# 6_Power_Output.net
KiCad netlist of a schematic drawn in Altium Designer
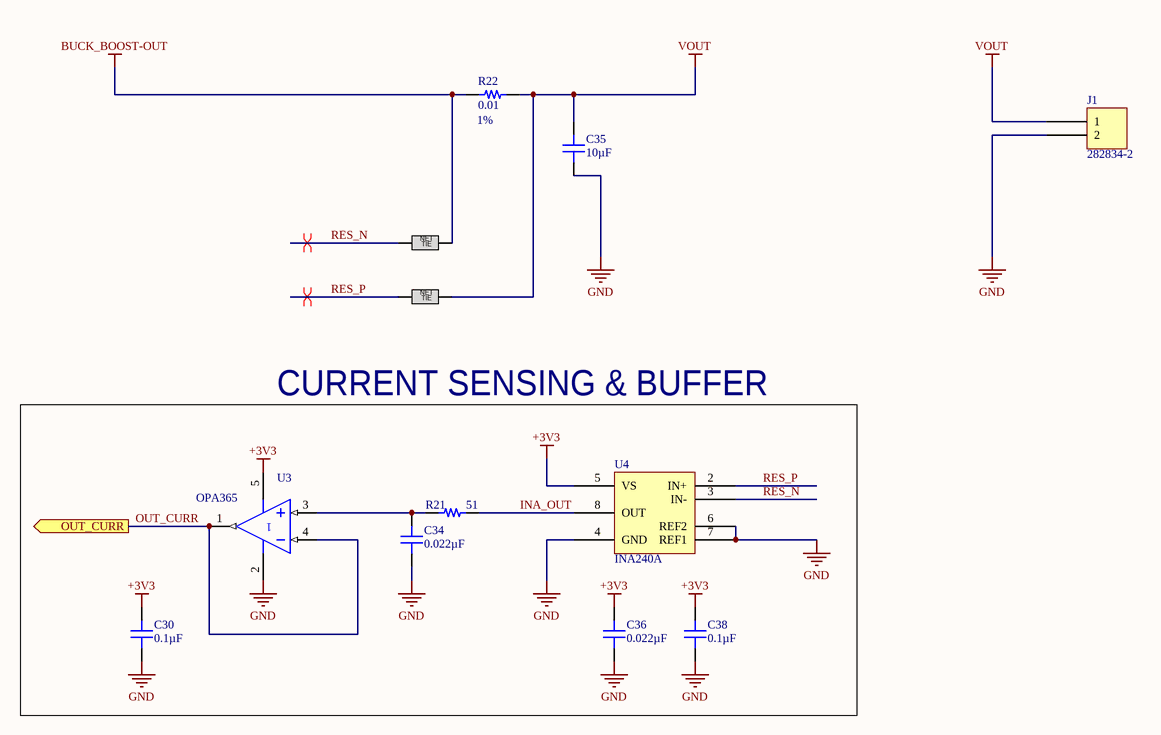
[diagram p0: [6] Power Output.SchDoc]

(export (version "E")
  (design (tool "Eeschema 10.0.6"))
  (components
    (comp (ref "C30")
      (value "0.1µF")
      (footprint "CAP 0805_2012")
      (description "CAP CER 0.1UF 16V X7R 0805")
      (fields
        (field (name "PART NUMBER") "160R15W104KV4T")
        (field (name "MANUFACTURER") "Johanson Dielectrics Inc.")
      )
      (libsource (lib "Celestial Altium Library - altium_library") (part "Capacitor"))
    )
    (comp (ref "C34")
      (value "0.022µF")
      (footprint "CAP 0603_1608")
      (description "CAP CER 0.022UF 25V X7R 0603")
      (fields
        (field (name "PART NUMBER") "0603B223J250CT")
        (field (name "MANUFACTURER") "Walsin Technology Corporation")
      )
      (libsource (lib "Celestial Altium Library - altium_library") (part "Capacitor"))
    )
    (comp (ref "C35")
      (value "10µF")
      (footprint "CAP 2220_5650 2.5MM")
      (description "CAP CER 10UF 50V X7R 2220")
      (fields
        (field (name "PART NUMBER") "C5750X7R1H106M230KB")
        (field (name "MANUFACTURER") "TDK Corporation")
      )
      (libsource (lib "Celestial Altium Library - altium_library") (part "Capacitor"))
    )
    (comp (ref "C36")
      (value "0.022µF")
      (footprint "CAP 0603_1608")
      (description "CAP CER 0.022UF 25V X7R 0603")
      (fields
        (field (name "PART NUMBER") "0603B223J250CT")
        (field (name "MANUFACTURER") "Walsin Technology Corporation")
      )
      (libsource (lib "Celestial Altium Library - altium_library") (part "Capacitor"))
    )
    (comp (ref "C38")
      (value "0.1µF")
      (footprint "CAP 0805_2012")
      (description "CAP CER 0.1UF 16V X7R 0805")
      (fields
        (field (name "PART NUMBER") "160R15W104KV4T")
        (field (name "MANUFACTURER") "Johanson Dielectrics Inc.")
      )
      (libsource (lib "Celestial Altium Library - altium_library") (part "Capacitor"))
    )
    (comp (ref "J1")
      (value "282834-2")
      (footprint "TE 282834-2")
      (description "TERM BLK 2P SIDE ENT 2.54MM PCB")
      (fields (field (name "MANUFACTURER") "TE Connectivity AMP Connectors") (field (name "VOLTAGE") "150V"))
      (libsource (lib "Celestial Altium Library - altium_library") (part "2 Pin"))
    )
    (comp (ref "NetTie3")
      (value "Net Tie")
      (footprint "3D FootPrint_Backup:Net_Tie_2x0.156mm")
      (libsource (lib "Altium Component") (part "Net Tie"))
    )
    (comp (ref "NetTie4")
      (value "Net Tie")
      (footprint "3D FootPrint_Backup:Net_Tie_2x0.156mm")
      (libsource (lib "Altium Component") (part "Net Tie"))
    )
    (comp (ref "R21")
      (value "51")
      (footprint "RES 0603/1608")
      (description "RES SMD 51 OHM 1% 1/10W 0603")
      (fields
        (field (name "PART NUMBER") "ERJ-3EKF51R0V")
        (field (name "MANUFACTURER") "Panasonic Electronic Components")
      )
      (libsource (lib "Celestial Library Database") (part "Resistor"))
    )
    (comp (ref "R22")
      (value "0.01")
      (footprint "STACKPOLE CSR2512")
      (description "RES SMD 0.01 OHM 1% 2W 2512")
      (fields
        (field (name "PART NUMBER") "CSR2512FK10L0")
        (field (name "MANUFACTURER") "Stackpole Electronics Inc.")
        (field (name "TOLERANCE") "1%")
      )
      (libsource (lib "Celestial Library Database") (part "Resistor"))
    )
    (comp (ref "U3")
      (value "OPA365")
      (footprint "DIODES SOT-23-5 W5")
      (description "RAIL-TO-RAIL OPAMP SOT-23-5")
      (fields (field (name "PART NUMBER") "TSV911ILT") (field (name "PUBLISHER") "Altium Limited"))
      (libsource (lib "Celestial Library Database") (part "TSV911ILT"))
    )
    (comp (ref "U4")
      (value "INA240A")
      (footprint "Atmel TSSOP-8 8X")
      (description "IC AMP CURRENT SENSE 8-TSSOP")
      (libsource (lib "Celestial Library Database") (part "INA240"))
    )
  )
  (nets
    (net (code "1") (name "+3V3") (class "Default")
      (node (ref "C30") (pin "2") (pinfunction "2_2") (pintype "passive"))
      (node (ref "C36") (pin "2") (pinfunction "2_2") (pintype "passive"))
      (node (ref "C38") (pin "2") (pinfunction "2_2") (pintype "passive"))
      (node (ref "U3") (pin "5") (pinfunction "V-_5") (pintype "power_in"))
      (node (ref "U4") (pin "5") (pinfunction "VS_5") (pintype "passive"))
    )
    (net (code "2") (name "/INA_OUT") (class "Default")
      (node (ref "R21") (pin "2") (pinfunction "2_2") (pintype "passive"))
      (node (ref "U4") (pin "8") (pinfunction "OUT_8") (pintype "passive"))
    )
    (net (code "3") (name "/OUT_CURR") (class "Default")
      (node (ref "U3") (pin "1") (pinfunction "OUT_1") (pintype "output"))
      (node (ref "U3") (pin "4") (pinfunction "IN-_4") (pintype "input"))
    )
    (net (code "4") (name "/RES_N") (class "Default")
      (node (ref "NetTie3") (pin "1") (pinfunction "1_1") (pintype "passive"))
      (node (ref "U4") (pin "3") (pinfunction "IN-_3") (pintype "passive"))
    )
    (net (code "5") (name "/RES_P") (class "Default")
      (node (ref "NetTie4") (pin "1") (pinfunction "1_1") (pintype "passive"))
      (node (ref "U4") (pin "2") (pinfunction "IN+_2") (pintype "passive"))
    )
    (net (code "6") (name "BUCK_BOOST-OUT") (class "Default")
      (node (ref "NetTie3") (pin "2") (pinfunction "2_2") (pintype "passive"))
      (node (ref "R22") (pin "1") (pinfunction "1_1") (pintype "passive"))
    )
    (net (code "7") (name "GND") (class "Default")
      (node (ref "C30") (pin "1") (pinfunction "1_1") (pintype "passive"))
      (node (ref "C34") (pin "1") (pinfunction "1_1") (pintype "passive"))
      (node (ref "C35") (pin "1") (pinfunction "1_1") (pintype "passive"))
      (node (ref "C36") (pin "1") (pinfunction "1_1") (pintype "passive"))
      (node (ref "C38") (pin "1") (pinfunction "1_1") (pintype "passive"))
      (node (ref "J1") (pin "2") (pinfunction "2_2") (pintype "passive"))
      (node (ref "U3") (pin "2") (pinfunction "V+_2") (pintype "power_in"))
      (node (ref "U4") (pin "4") (pinfunction "GND_4") (pintype "passive"))
      (node (ref "U4") (pin "6") (pinfunction "REF2_6") (pintype "passive"))
      (node (ref "U4") (pin "7") (pinfunction "REF1_7") (pintype "passive"))
    )
    (net (code "8") (name "Net-(U3-IN+)") (class "Default")
      (node (ref "C34") (pin "2") (pinfunction "2_2") (pintype "passive"))
      (node (ref "R21") (pin "1") (pinfunction "1_1") (pintype "passive"))
      (node (ref "U3") (pin "3") (pinfunction "IN+_3") (pintype "input"))
    )
    (net (code "9") (name "VOUT") (class "Default")
      (node (ref "C35") (pin "2") (pinfunction "2_2") (pintype "passive"))
      (node (ref "J1") (pin "1") (pinfunction "1_1") (pintype "passive"))
      (node (ref "NetTie4") (pin "2") (pinfunction "2_2") (pintype "passive"))
      (node (ref "R22") (pin "2") (pinfunction "2_2") (pintype "passive"))
    )
    (net (code "10") (name "unconnected-(U4-NC-Pad1)") (class "Default")
      (node (ref "U4") (pin "1") (pinfunction "NC_1") (pintype "passive"))
    )
  )
)
